# OpenBook_Schematic.net
KiCad netlist of a schematic drawn in EAGLE
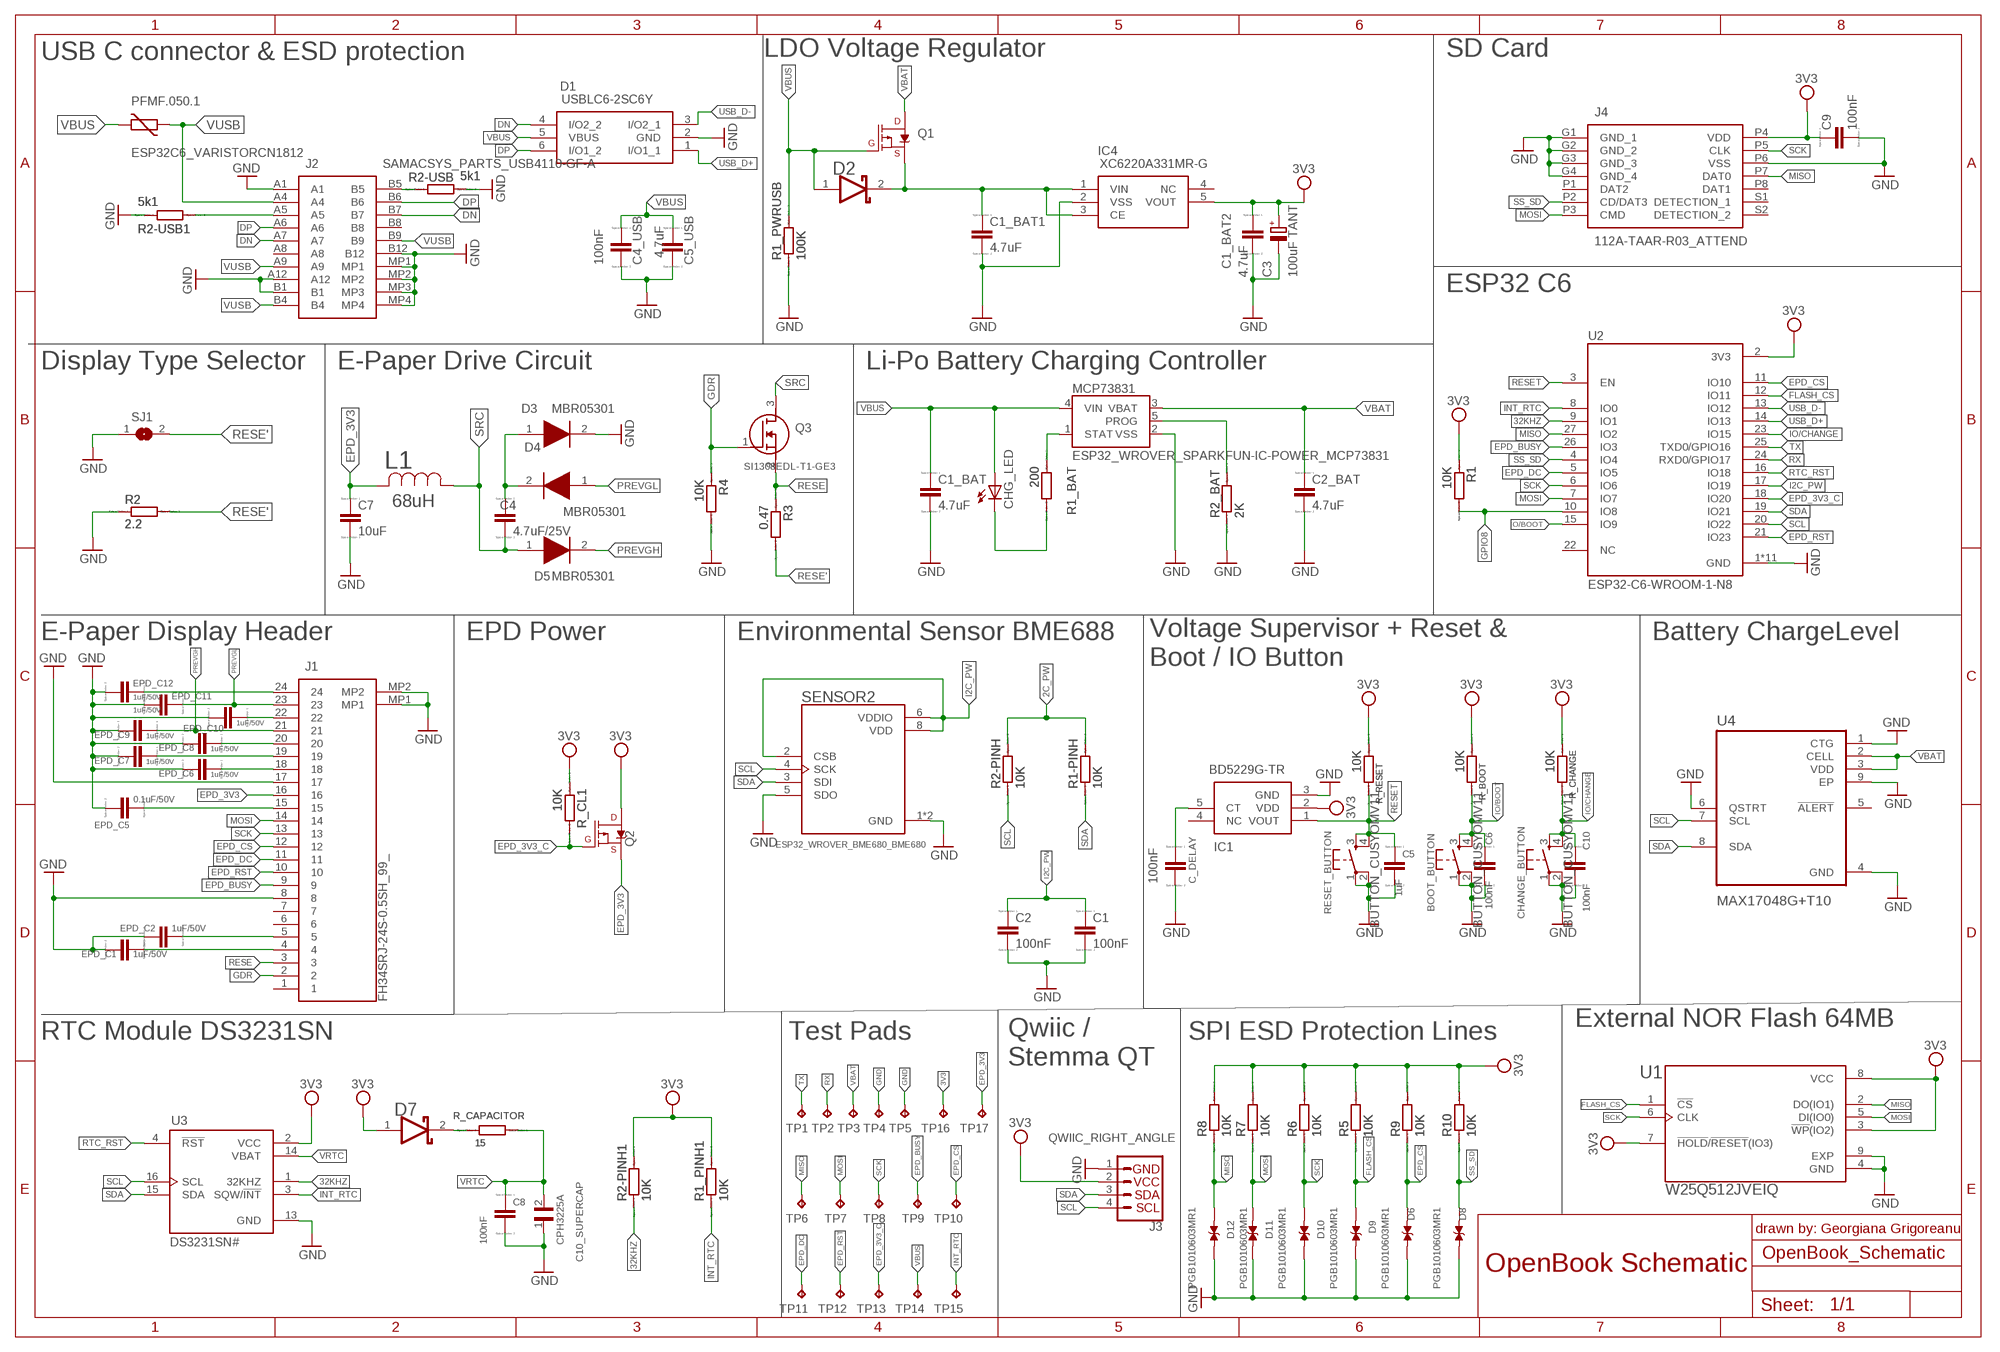
[diagram p0: schematic, sheet 1]

(export (version "E")
  (design (tool "Eeschema 10.0.6"))
  (components
    (comp (ref "BOOT_BUTTON")
      (value "BUTTON_CUSYOMV11")
      (footprint "eagle-import:MYBUTTON")
      (libsource (lib "eagle-import") (part "BUTTON_CUSYOMV11"))
    )
    (comp (ref "C1")
      (value "100nF")
      (footprint "eagle-import:ESP32_WROVER_EAGLE-LTSPICE_C0402")
      (libsource (lib "eagle-import") (part "ESP32_WROVER_EAGLE-LTSPICE_C"))
    )
    (comp (ref "C1_BAT")
      (value "4.7uF")
      (footprint "eagle-import:ESP32_WROVER_EAGLE-LTSPICE_C0402")
      (libsource (lib "eagle-import") (part "ESP32_WROVER_EAGLE-LTSPICE_C"))
    )
    (comp (ref "C1_BAT1")
      (value "4.7uF")
      (footprint "eagle-import:ESP32_WROVER_EAGLE-LTSPICE_C0402")
      (libsource (lib "eagle-import") (part "ESP32_WROVER_EAGLE-LTSPICE_C"))
    )
    (comp (ref "C1_BAT2")
      (value "4.7uF")
      (footprint "eagle-import:ESP32_WROVER_EAGLE-LTSPICE_C0402")
      (libsource (lib "eagle-import") (part "ESP32_WROVER_EAGLE-LTSPICE_C"))
    )
    (comp (ref "C2")
      (value "100nF")
      (footprint "eagle-import:ESP32_WROVER_EAGLE-LTSPICE_C0402")
      (libsource (lib "eagle-import") (part "ESP32_WROVER_EAGLE-LTSPICE_C"))
    )
    (comp (ref "C2_BAT")
      (value "4.7uF")
      (footprint "eagle-import:ESP32_WROVER_EAGLE-LTSPICE_C0402")
      (libsource (lib "eagle-import") (part "ESP32_WROVER_EAGLE-LTSPICE_C"))
    )
    (comp (ref "C3")
      (value "100uF TANT")
      (footprint "eagle-import:RCL_CT3528")
      (libsource (lib "eagle-import") (part "RCL_CPOL-EUCT3528"))
    )
    (comp (ref "C4")
      (value "4.7uF/25V")
      (footprint "eagle-import:ESP32_WROVER_EAGLE-LTSPICE_C0402")
      (libsource (lib "eagle-import") (part "ESP32_WROVER_EAGLE-LTSPICE_C"))
    )
    (comp (ref "C4_USB")
      (value "100nF")
      (footprint "eagle-import:ESP32_WROVER_EAGLE-LTSPICE_C0402")
      (libsource (lib "eagle-import") (part "ESP32_WROVER_EAGLE-LTSPICE_C"))
    )
    (comp (ref "C5")
      (value "1uF")
      (footprint "eagle-import:ESP32_WROVER_EAGLE-LTSPICE_C0402")
      (libsource (lib "eagle-import") (part "ESP32_WROVER_EAGLE-LTSPICE_C"))
    )
    (comp (ref "C5_USB")
      (value "4.7uF")
      (footprint "eagle-import:ESP32_WROVER_EAGLE-LTSPICE_C0402")
      (libsource (lib "eagle-import") (part "ESP32_WROVER_EAGLE-LTSPICE_C"))
    )
    (comp (ref "C6")
      (value "100nF")
      (footprint "eagle-import:ESP32_WROVER_EAGLE-LTSPICE_C0402")
      (libsource (lib "eagle-import") (part "ESP32_WROVER_EAGLE-LTSPICE_C"))
    )
    (comp (ref "C7")
      (value "10uF")
      (footprint "eagle-import:ESP32_WROVER_EAGLE-LTSPICE_C0402")
      (libsource (lib "eagle-import") (part "ESP32_WROVER_EAGLE-LTSPICE_C"))
    )
    (comp (ref "C8")
      (value "100nF")
      (footprint "eagle-import:ESP32_WROVER_EAGLE-LTSPICE_C0402")
      (libsource (lib "eagle-import") (part "ESP32_WROVER_EAGLE-LTSPICE_C"))
    )
    (comp (ref "C9")
      (value "100nF")
      (footprint "eagle-import:ESP32_WROVER_EAGLE-LTSPICE_C0402")
      (libsource (lib "eagle-import") (part "ESP32_WROVER_EAGLE-LTSPICE_C"))
    )
    (comp (ref "C10")
      (value "100nF")
      (footprint "eagle-import:ESP32_WROVER_EAGLE-LTSPICE_C0402")
      (libsource (lib "eagle-import") (part "ESP32_WROVER_EAGLE-LTSPICE_C"))
    )
    (comp (ref "C10_SUPERCAP")
      (value "CPH3225A")
      (footprint "eagle-import:CAPCP3225X100N")
      (fields (field (name "MF") "Seiko Instruments"))
      (libsource (lib "eagle-import") (part "CPH3225A"))
    )
    (comp (ref "CHANGE_BUTTON")
      (value "BUTTON_CUSYOMV11")
      (footprint "eagle-import:MYBUTTON")
      (libsource (lib "eagle-import") (part "BUTTON_CUSYOMV11"))
    )
    (comp (ref "CHG_LED")
      (value "ADAFRUIT_LEDCHIP-LED0603")
      (footprint "eagle-import:ADAFRUIT_CHIP-LED0603")
      (libsource (lib "eagle-import") (part "ADAFRUIT_LEDCHIP-LED0603"))
    )
    (comp (ref "C_DELAY")
      (value "100nF")
      (footprint "eagle-import:ESP32_WROVER_EAGLE-LTSPICE_C0402")
      (libsource (lib "eagle-import") (part "ESP32_WROVER_EAGLE-LTSPICE_C"))
    )
    (comp (ref "D1")
      (value "USBLC6-2SC6Y")
      (footprint "eagle-import:SOT95P280X145-6N")
      (fields (field (name "MF") "STMicroelectronics"))
      (libsource (lib "eagle-import") (part "USBLC6-2SC6Y"))
    )
    (comp (ref "D2")
      (value "ESP32_WROVER_AVX---SD0805S020S1R0_AVX_SD0805S020S1R0_0_0")
      (footprint "eagle-import:ESP32_WROVER_AVX---SD0805S020S1R0_AVX_SD0805S020S1R0_0")
      (libsource (lib "eagle-import") (part "ESP32_WROVER_AVX---SD0805S020S1R0_AVX_SD0805S020S1R0_0_0"))
    )
    (comp (ref "D3")
      (value "MBR05301")
      (footprint "eagle-import:SOD3716X135N")
      (libsource (lib "eagle-import") (part "MBR05301"))
    )
    (comp (ref "D4")
      (value "MBR05301")
      (footprint "eagle-import:SOD3716X135N")
      (libsource (lib "eagle-import") (part "MBR05301"))
    )
    (comp (ref "D5")
      (value "MBR05301")
      (footprint "eagle-import:SOD3716X135N")
      (libsource (lib "eagle-import") (part "MBR05301"))
    )
    (comp (ref "D6")
      (value "PGB1010603MR1")
      (footprint "eagle-import:DIOC1608X36N")
      (libsource (lib "eagle-import") (part "PGB1010603MR1"))
    )
    (comp (ref "D7")
      (value "ESP32_WROVER_AVX---SD0805S020S1R0_AVX_SD0805S020S1R0_0_0")
      (footprint "eagle-import:ESP32_WROVER_AVX---SD0805S020S1R0_AVX_SD0805S020S1R0_0")
      (libsource (lib "eagle-import") (part "ESP32_WROVER_AVX---SD0805S020S1R0_AVX_SD0805S020S1R0_0_0"))
    )
    (comp (ref "D8")
      (value "PGB1010603MR1")
      (footprint "eagle-import:DIOC1608X36N")
      (libsource (lib "eagle-import") (part "PGB1010603MR1"))
    )
    (comp (ref "D9")
      (value "PGB1010603MR1")
      (footprint "eagle-import:DIOC1608X36N")
      (libsource (lib "eagle-import") (part "PGB1010603MR1"))
    )
    (comp (ref "D10")
      (value "PGB1010603MR1")
      (footprint "eagle-import:DIOC1608X36N")
      (libsource (lib "eagle-import") (part "PGB1010603MR1"))
    )
    (comp (ref "D11")
      (value "PGB1010603MR1")
      (footprint "eagle-import:DIOC1608X36N")
      (libsource (lib "eagle-import") (part "PGB1010603MR1"))
    )
    (comp (ref "D12")
      (value "PGB1010603MR1")
      (footprint "eagle-import:DIOC1608X36N")
      (libsource (lib "eagle-import") (part "PGB1010603MR1"))
    )
    (comp (ref "EPD_C1")
      (value "1uF/50V")
      (footprint "eagle-import:ESP32_WROVER_EAGLE-LTSPICE_C0402")
      (libsource (lib "eagle-import") (part "ESP32_WROVER_EAGLE-LTSPICE_C"))
    )
    (comp (ref "EPD_C2")
      (value "1uF/50V")
      (footprint "eagle-import:ESP32_WROVER_EAGLE-LTSPICE_C0402")
      (libsource (lib "eagle-import") (part "ESP32_WROVER_EAGLE-LTSPICE_C"))
    )
    (comp (ref "EPD_C5")
      (value "0.1uF/50V")
      (footprint "eagle-import:ESP32_WROVER_EAGLE-LTSPICE_C0402")
      (libsource (lib "eagle-import") (part "ESP32_WROVER_EAGLE-LTSPICE_C"))
    )
    (comp (ref "EPD_C6")
      (value "1uF/50V")
      (footprint "eagle-import:ESP32_WROVER_EAGLE-LTSPICE_C0402")
      (libsource (lib "eagle-import") (part "ESP32_WROVER_EAGLE-LTSPICE_C"))
    )
    (comp (ref "EPD_C7")
      (value "1uF/50V")
      (footprint "eagle-import:ESP32_WROVER_EAGLE-LTSPICE_C0402")
      (libsource (lib "eagle-import") (part "ESP32_WROVER_EAGLE-LTSPICE_C"))
    )
    (comp (ref "EPD_C8")
      (value "1uF/50V")
      (footprint "eagle-import:ESP32_WROVER_EAGLE-LTSPICE_C0402")
      (libsource (lib "eagle-import") (part "ESP32_WROVER_EAGLE-LTSPICE_C"))
    )
    (comp (ref "EPD_C9")
      (value "1uF/50V")
      (footprint "eagle-import:ESP32_WROVER_EAGLE-LTSPICE_C0402")
      (libsource (lib "eagle-import") (part "ESP32_WROVER_EAGLE-LTSPICE_C"))
    )
    (comp (ref "EPD_C10")
      (value "1uF/50V")
      (footprint "eagle-import:ESP32_WROVER_EAGLE-LTSPICE_C0402")
      (libsource (lib "eagle-import") (part "ESP32_WROVER_EAGLE-LTSPICE_C"))
    )
    (comp (ref "EPD_C11")
      (value "1uF/50V")
      (footprint "eagle-import:ESP32_WROVER_EAGLE-LTSPICE_C0402")
      (libsource (lib "eagle-import") (part "ESP32_WROVER_EAGLE-LTSPICE_C"))
    )
    (comp (ref "EPD_C12")
      (value "1uF/50V")
      (footprint "eagle-import:ESP32_WROVER_EAGLE-LTSPICE_C0402")
      (libsource (lib "eagle-import") (part "ESP32_WROVER_EAGLE-LTSPICE_C"))
    )
    (comp (ref "IC1")
      (value "BD5229G-TR")
      (footprint "eagle-import:SOT95P280X125-5N")
      (fields (field (name "MOUSER_PART_NUMBER") "755-BD5229G-TR"))
      (libsource (lib "eagle-import") (part "BD5229G-TR"))
    )
    (comp (ref "IC4")
      (value "XC6220A331MR-G")
      (footprint "eagle-import:SOT95P280X120-5N")
      (fields (field (name "MOUSER_PART_NUMBER") "865-XC6220A331MR-G"))
      (libsource (lib "eagle-import") (part "XC6220A331MR-G"))
    )
    (comp (ref "J1")
      (value "FH34SRJ-24S-0.5SH_99_")
      (footprint "eagle-import:FH34SRJ24S05SH99")
      (fields
        (field (name "MANUFACTURER_PART_NUMBER") "FH34SRJ-24S-0.5SH(99)")
        (field (name "MOUSER_PART_NUMBER") "798-FH34SRJ24S05SH99")
      )
      (libsource (lib "eagle-import") (part "FH34SRJ-24S-0.5SH_99_"))
    )
    (comp (ref "J2")
      (value "SAMACSYS_PARTS_USB4110-GF-A")
      (footprint "eagle-import:SAMACSYS_PARTS_USB4110GFA")
      (fields
        (field (name "MANUFACTURER_PART_NUMBER") "USB4110-GF-A")
        (field (name "MOUSER_PART_NUMBER") "640-USB4110-GF-A")
      )
      (libsource (lib "eagle-import") (part "SAMACSYS_PARTS_USB4110-GF-A"))
    )
    (comp (ref "J3")
      (value "QWIIC_RIGHT_ANGLE")
      (footprint "eagle-import:JST04_1MM_RA")
      (libsource (lib "eagle-import") (part "QWIIC_CONNECTORJS-1MM"))
    )
    (comp (ref "J4")
      (value "112A-TAAR-R03_ATTEND")
      (footprint "eagle-import:112ATAARR03ATTEND")
      (fields (field (name "MANUFACTURER_PART_NUMBER") "112A-TAAR-R03 ATTEND"))
      (libsource (lib "eagle-import") (part "112A-TAAR-R03_ATTEND"))
    )
    (comp (ref "L1")
      (value "68uH")
      (footprint "eagle-import:IND_4828-WE-TPC_WRE")
      (fields
        (field (name "MANUFACTURER_PART_NUMBER") "744043680")
        (field (name "COPYRIGHT") "Copyright (C) 2024 Ultra Librarian. All rights reserved.")
      )
      (libsource (lib "eagle-import") (part "744043680IND_4828-WE-TPC_WRE"))
    )
    (comp (ref "MCP73831")
      (value "ESP32_WROVER_SPARKFUN-IC-POWER_MCP73831")
      (footprint "eagle-import:ESP32_WROVER_SPARKFUN-IC-POWER_SOT23-5")
      (libsource (lib "eagle-import") (part "ESP32_WROVER_SPARKFUN-IC-POWER_MCP73831"))
    )
    (comp (ref "PFMF.050.1")
      (value "ESP32C6_VARISTORCN1812")
      (footprint "eagle-import:ESP32C6_VARISTOR_CT_CN1812")
      (libsource (lib "eagle-import") (part "ESP32C6_VARISTORCN1812"))
    )
    (comp (ref "Q1")
      (value "20V/4.2A/52mΩ/1.4W")
      (footprint "eagle-import:ESP32_WROVER_SPARKFUN-DISCRETESEMI_SOT23-3")
      (libsource (lib "eagle-import") (part "ESP32_WROVER_SPARKFUN-DISCRETESEMI_MOSFET_PCH"))
    )
    (comp (ref "Q2")
      (value "20V/4.2A/52mΩ/1.4W")
      (footprint "eagle-import:ESP32_WROVER_SPARKFUN-DISCRETESEMI_SOT23-3")
      (libsource (lib "eagle-import") (part "ESP32_WROVER_SPARKFUN-DISCRETESEMI_MOSFET_PCH"))
    )
    (comp (ref "Q3")
      (value "SI1308EDL-T1-GE3")
      (footprint "eagle-import:SOT65P210X110-3N")
      (fields (field (name "MF") "Vishay Siliconix"))
      (libsource (lib "eagle-import") (part "SI1308EDL-T1-GE3"))
    )
    (comp (ref "R1")
      (value "10K")
      (footprint "eagle-import:ESP32_WROVER_EAGLE-LTSPICE_C0402")
      (libsource (lib "eagle-import") (part "ESP32_WROVER_EAGLE-LTSPICE_R1"))
    )
    (comp (ref "R1-PINH")
      (value "10K")
      (footprint "eagle-import:ESP32_WROVER_EAGLE-LTSPICE_C0402")
      (libsource (lib "eagle-import") (part "ESP32_WROVER_EAGLE-LTSPICE_R1"))
    )
    (comp (ref "R1_BAT")
      (value "200")
      (footprint "eagle-import:ESP32_WROVER_EAGLE-LTSPICE_C0402")
      (libsource (lib "eagle-import") (part "ESP32_WROVER_EAGLE-LTSPICE_R1"))
    )
    (comp (ref "R1_PINH1")
      (value "10K")
      (footprint "eagle-import:ESP32_WROVER_EAGLE-LTSPICE_C0402")
      (libsource (lib "eagle-import") (part "ESP32_WROVER_EAGLE-LTSPICE_R1"))
    )
    (comp (ref "R1_PWRUSB")
      (value "100K")
      (footprint "eagle-import:ESP32_WROVER_EAGLE-LTSPICE_C0402")
      (libsource (lib "eagle-import") (part "ESP32_WROVER_EAGLE-LTSPICE_R1"))
    )
    (comp (ref "R2")
      (value "2.2")
      (footprint "eagle-import:ESP32_WROVER_EAGLE-LTSPICE_C0402")
      (libsource (lib "eagle-import") (part "ESP32_WROVER_EAGLE-LTSPICE_R1"))
    )
    (comp (ref "R2-PINH")
      (value "10K")
      (footprint "eagle-import:ESP32_WROVER_EAGLE-LTSPICE_C0402")
      (libsource (lib "eagle-import") (part "ESP32_WROVER_EAGLE-LTSPICE_R1"))
    )
    (comp (ref "R2-PINH1")
      (value "10K")
      (footprint "eagle-import:ESP32_WROVER_EAGLE-LTSPICE_C0402")
      (libsource (lib "eagle-import") (part "ESP32_WROVER_EAGLE-LTSPICE_R1"))
    )
    (comp (ref "R2-USB")
      (value "5k1")
      (footprint "eagle-import:ESP32_WROVER_EAGLE-LTSPICE_C0402")
      (libsource (lib "eagle-import") (part "ESP32_WROVER_EAGLE-LTSPICE_R1"))
    )
    (comp (ref "R2-USB1")
      (value "5k1")
      (footprint "eagle-import:ESP32_WROVER_EAGLE-LTSPICE_C0402")
      (libsource (lib "eagle-import") (part "ESP32_WROVER_EAGLE-LTSPICE_R1"))
    )
    (comp (ref "R2_BAT")
      (value "2K")
      (footprint "eagle-import:ESP32_WROVER_EAGLE-LTSPICE_C0402")
      (libsource (lib "eagle-import") (part "ESP32_WROVER_EAGLE-LTSPICE_R1"))
    )
    (comp (ref "R3")
      (value "0.47")
      (footprint "eagle-import:ESP32_WROVER_EAGLE-LTSPICE_C0402")
      (libsource (lib "eagle-import") (part "ESP32_WROVER_EAGLE-LTSPICE_R1"))
    )
    (comp (ref "R4")
      (value "10K")
      (footprint "eagle-import:ESP32_WROVER_EAGLE-LTSPICE_C0402")
      (libsource (lib "eagle-import") (part "ESP32_WROVER_EAGLE-LTSPICE_R1"))
    )
    (comp (ref "R5")
      (value "10K")
      (footprint "eagle-import:ESP32_WROVER_EAGLE-LTSPICE_C0402")
      (libsource (lib "eagle-import") (part "ESP32_WROVER_EAGLE-LTSPICE_R1"))
    )
    (comp (ref "R6")
      (value "10K")
      (footprint "eagle-import:ESP32_WROVER_EAGLE-LTSPICE_C0402")
      (libsource (lib "eagle-import") (part "ESP32_WROVER_EAGLE-LTSPICE_R1"))
    )
    (comp (ref "R7")
      (value "10K")
      (footprint "eagle-import:ESP32_WROVER_EAGLE-LTSPICE_C0402")
      (libsource (lib "eagle-import") (part "ESP32_WROVER_EAGLE-LTSPICE_R1"))
    )
    (comp (ref "R8")
      (value "10K")
      (footprint "eagle-import:ESP32_WROVER_EAGLE-LTSPICE_C0402")
      (libsource (lib "eagle-import") (part "ESP32_WROVER_EAGLE-LTSPICE_R1"))
    )
    (comp (ref "R9")
      (value "10K")
      (footprint "eagle-import:ESP32_WROVER_EAGLE-LTSPICE_C0402")
      (libsource (lib "eagle-import") (part "ESP32_WROVER_EAGLE-LTSPICE_R1"))
    )
    (comp (ref "R10")
      (value "10K")
      (footprint "eagle-import:ESP32_WROVER_EAGLE-LTSPICE_C0402")
      (libsource (lib "eagle-import") (part "ESP32_WROVER_EAGLE-LTSPICE_R1"))
    )
    (comp (ref "RESET_BUTTON")
      (value "BUTTON_CUSYOMV11")
      (footprint "eagle-import:MYBUTTON")
      (libsource (lib "eagle-import") (part "BUTTON_CUSYOMV11"))
    )
    (comp (ref "R_BOOT")
      (value "10K")
      (footprint "eagle-import:ESP32_WROVER_EAGLE-LTSPICE_C0402")
      (libsource (lib "eagle-import") (part "ESP32_WROVER_EAGLE-LTSPICE_R1"))
    )
    (comp (ref "R_CAPACITOR")
      (value "15")
      (footprint "eagle-import:ESP32_WROVER_EAGLE-LTSPICE_C0402")
      (libsource (lib "eagle-import") (part "ESP32_WROVER_EAGLE-LTSPICE_R1"))
    )
    (comp (ref "R_CHANGE")
      (value "10K")
      (footprint "eagle-import:ESP32_WROVER_EAGLE-LTSPICE_C0402")
      (libsource (lib "eagle-import") (part "ESP32_WROVER_EAGLE-LTSPICE_R1"))
    )
    (comp (ref "R_CL1")
      (value "10K")
      (footprint "eagle-import:ESP32_WROVER_EAGLE-LTSPICE_C0402")
      (libsource (lib "eagle-import") (part "ESP32_WROVER_EAGLE-LTSPICE_R1"))
    )
    (comp (ref "R_RESET")
      (value "10K")
      (footprint "eagle-import:ESP32_WROVER_EAGLE-LTSPICE_C0402")
      (libsource (lib "eagle-import") (part "ESP32_WROVER_EAGLE-LTSPICE_R1"))
    )
    (comp (ref "SENSOR2")
      (value "ESP32_WROVER_BME680_BME680")
      (footprint "eagle-import:ESP32_WROVER_BME680_PSON80P300X300X100-8N")
      (fields (field (name "MF") "Bosch Sensortec") (field (name "MP") "BME680"))
      (libsource (lib "eagle-import") (part "ESP32_WROVER_BME680_BME680"))
    )
    (comp (ref "SJ1") (value "SJ") (footprint "eagle-import:SJ") (libsource (lib "eagle-import") (part "SJ")))
    (comp (ref "TP1")
      (value "TP")
      (footprint "eagle-import:TP20R")
      (libsource (lib "eagle-import") (part "TP"))
    )
    (comp (ref "TP2")
      (value "TP")
      (footprint "eagle-import:TP20R")
      (libsource (lib "eagle-import") (part "TP"))
    )
    (comp (ref "TP3")
      (value "TP")
      (footprint "eagle-import:TP20R")
      (libsource (lib "eagle-import") (part "TP"))
    )
    (comp (ref "TP4")
      (value "TP")
      (footprint "eagle-import:TP20R")
      (libsource (lib "eagle-import") (part "TP"))
    )
    (comp (ref "TP5")
      (value "TP")
      (footprint "eagle-import:TP20R")
      (libsource (lib "eagle-import") (part "TP"))
    )
    (comp (ref "TP6")
      (value "TP")
      (footprint "eagle-import:TP20R")
      (libsource (lib "eagle-import") (part "TP"))
    )
    (comp (ref "TP7")
      (value "TP")
      (footprint "eagle-import:TP20R")
      (libsource (lib "eagle-import") (part "TP"))
    )
    (comp (ref "TP8")
      (value "TP")
      (footprint "eagle-import:TP20R")
      (libsource (lib "eagle-import") (part "TP"))
    )
    (comp (ref "TP9")
      (value "TP")
      (footprint "eagle-import:TP20R")
      (libsource (lib "eagle-import") (part "TP"))
    )
    (comp (ref "TP10")
      (value "TP")
      (footprint "eagle-import:TP20R")
      (libsource (lib "eagle-import") (part "TP"))
    )
    (comp (ref "TP11")
      (value "TP")
      (footprint "eagle-import:TP20R")
      (libsource (lib "eagle-import") (part "TP"))
    )
    (comp (ref "TP12")
      (value "TP")
      (footprint "eagle-import:TP20R")
      (libsource (lib "eagle-import") (part "TP"))
    )
    (comp (ref "TP13")
      (value "TP")
      (footprint "eagle-import:TP20R")
      (libsource (lib "eagle-import") (part "TP"))
    )
    (comp (ref "TP14")
      (value "TP")
      (footprint "eagle-import:TP20R")
      (libsource (lib "eagle-import") (part "TP"))
    )
    (comp (ref "TP15")
      (value "TP")
      (footprint "eagle-import:TP20R")
      (libsource (lib "eagle-import") (part "TP"))
    )
    (comp (ref "TP16")
      (value "TP")
      (footprint "eagle-import:TP20R")
      (libsource (lib "eagle-import") (part "TP"))
    )
    (comp (ref "TP17")
      (value "TP")
      (footprint "eagle-import:TP20R")
      (libsource (lib "eagle-import") (part "TP"))
    )
    (comp (ref "U1")
      (value "W25Q512JVEIQ")
      (footprint "eagle-import:SON127P600X800X80-9N")
      (fields (field (name "MF") "Winbond Electronics"))
      (libsource (lib "eagle-import") (part "W25Q512JVEIQ"))
    )
    (comp (ref "U2")
      (value "ESP32-C6-WROOM-1-N8")
      (footprint "eagle-import:XCVR_ESP32-C6-WROOM-1-N8")
      (fields (field (name "MF") "Espressif Systems"))
      (libsource (lib "eagle-import") (part "ESP32-C6-WROOM-1-N8"))
    )
    (comp (ref "U3")
      (value "DS3231SN#")
      (footprint "eagle-import:SOIC127P1032X265-16N")
      (fields (field (name "MF") "Analog Devices"))
      (libsource (lib "eagle-import") (part "DS3231SN#"))
    )
    (comp (ref "U4")
      (value "MAX17048G+T10")
      (footprint "eagle-import:SON50P200X200X80-9N")
      (fields (field (name "MF") "Analog Devices"))
      (libsource (lib "eagle-import") (part "MAX17048G+T10"))
    )
  )
  (nets
    (net (code "1") (name "2C_PW") (class "Default")
      (node (ref "R1-PINH") (pin "2") (pinfunction "2_2") (pintype "passive"))
      (node (ref "R2-PINH") (pin "2") (pinfunction "2_2") (pintype "passive"))
    )
    (net (code "2") (name "3V3") (class "Default")
      (node (ref "C1_BAT2") (pin "1") (pinfunction "1_1") (pintype "passive"))
      (node (ref "C3") (pin "+") (pinfunction "+_+") (pintype "passive"))
      (node (ref "C9") (pin "1") (pinfunction "1_1") (pintype "passive"))
      (node (ref "D7") (pin "1") (pinfunction "ANODE_1") (pintype "bidirectional"))
      (node (ref "IC1") (pin "2") (pinfunction "VDD_2") (pintype "bidirectional"))
      (node (ref "IC4") (pin "5") (pinfunction "VOUT_5") (pintype "bidirectional"))
      (node (ref "J3") (pin "2") (pinfunction "2_2") (pintype "power_in"))
      (node (ref "J4") (pin "P4") (pinfunction "VDD_P4") (pintype "bidirectional"))
      (node (ref "Q2") (pin "1") (pinfunction "D_1") (pintype "bidirectional"))
      (node (ref "R1") (pin "1") (pinfunction "1_1") (pintype "passive"))
      (node (ref "R10") (pin "2") (pinfunction "2_2") (pintype "passive"))
      (node (ref "R1_PINH1") (pin "2") (pinfunction "2_2") (pintype "passive"))
      (node (ref "R2-PINH1") (pin "2") (pinfunction "2_2") (pintype "passive"))
      (node (ref "R5") (pin "2") (pinfunction "2_2") (pintype "passive"))
      (node (ref "R6") (pin "2") (pinfunction "2_2") (pintype "passive"))
      (node (ref "R7") (pin "2") (pinfunction "2_2") (pintype "passive"))
      (node (ref "R8") (pin "2") (pinfunction "2_2") (pintype "passive"))
      (node (ref "R9") (pin "2") (pinfunction "2_2") (pintype "passive"))
      (node (ref "R_BOOT") (pin "1") (pinfunction "1_1") (pintype "passive"))
      (node (ref "R_CHANGE") (pin "1") (pinfunction "1_1") (pintype "passive"))
      (node (ref "R_CL1") (pin "1") (pinfunction "1_1") (pintype "passive"))
      (node (ref "R_RESET") (pin "1") (pinfunction "1_1") (pintype "passive"))
      (node (ref "TP16") (pin "TP") (pinfunction "TP_TP") (pintype "input"))
      (node (ref "U1") (pin "3") (pinfunction "~{WP}(IO2)_3") (pintype "bidirectional"))
      (node (ref "U1") (pin "7") (pinfunction "~{HOLD}/~{RESET}(IO3)_7") (pintype "bidirectional"))
      (node (ref "U1") (pin "8") (pinfunction "VCC_8") (pintype "power_in"))
      (node (ref "U2") (pin "2") (pinfunction "3V3_2") (pintype "power_in"))
      (node (ref "U3") (pin "2") (pinfunction "VCC_2") (pintype "power_in"))
    )
    (net (code "3") (name "32KHZ") (class "Default")
      (node (ref "R2-PINH1") (pin "1") (pinfunction "1_1") (pintype "passive"))
      (node (ref "U2") (pin "9") (pinfunction "IO1_9") (pintype "bidirectional"))
      (node (ref "U3") (pin "1") (pinfunction "32KHZ_1") (pintype "output"))
    )
    (net (code "4") (name "DN") (class "Default")
      (node (ref "D1") (pin "4") (pinfunction "I/O2_2_4") (pintype "bidirectional"))
      (node (ref "J2") (pin "A7") (pinfunction "A7_A7") (pintype "bidirectional"))
      (node (ref "J2") (pin "B7") (pinfunction "B7_B7") (pintype "bidirectional"))
    )
    (net (code "5") (name "DP") (class "Default")
      (node (ref "D1") (pin "6") (pinfunction "I/O1_2_6") (pintype "bidirectional"))
      (node (ref "J2") (pin "A6") (pinfunction "A6_A6") (pintype "bidirectional"))
      (node (ref "J2") (pin "B6") (pinfunction "B6_B6") (pintype "bidirectional"))
    )
    (net (code "6") (name "EPD_3V3") (class "Default")
      (node (ref "C7") (pin "1") (pinfunction "1_1") (pintype "passive"))
      (node (ref "J1") (pin "16") (pinfunction "16_16") (pintype "bidirectional"))
      (node (ref "L1") (pin "2") (pinfunction "2_2") (pintype "passive"))
      (node (ref "Q2") (pin "3") (pinfunction "S_3") (pintype "bidirectional"))
      (node (ref "TP17") (pin "TP") (pinfunction "TP_TP") (pintype "input"))
    )
    (net (code "7") (name "EPD_3V3_C") (class "Default")
      (node (ref "Q2") (pin "2") (pinfunction "G_2") (pintype "bidirectional"))
      (node (ref "R_CL1") (pin "2") (pinfunction "2_2") (pintype "passive"))
      (node (ref "TP13") (pin "TP") (pinfunction "TP_TP") (pintype "input"))
      (node (ref "U2") (pin "18") (pinfunction "IO20_18") (pintype "bidirectional"))
    )
    (net (code "8") (name "EPD_BUSY") (class "Default")
      (node (ref "J1") (pin "9") (pinfunction "9_9") (pintype "bidirectional"))
      (node (ref "TP9") (pin "TP") (pinfunction "TP_TP") (pintype "input"))
      (node (ref "U2") (pin "26") (pinfunction "IO3_26") (pintype "bidirectional"))
    )
    (net (code "9") (name "EPD_CS") (class "Default")
      (node (ref "D6") (pin "1") (pinfunction "1_1") (pintype "passive"))
      (node (ref "J1") (pin "12") (pinfunction "12_12") (pintype "bidirectional"))
      (node (ref "R9") (pin "1") (pinfunction "1_1") (pintype "passive"))
      (node (ref "TP10") (pin "TP") (pinfunction "TP_TP") (pintype "input"))
      (node (ref "U2") (pin "11") (pinfunction "IO10_11") (pintype "bidirectional"))
    )
    (net (code "10") (name "EPD_DC") (class "Default")
      (node (ref "J1") (pin "11") (pinfunction "11_11") (pintype "bidirectional"))
      (node (ref "TP11") (pin "TP") (pinfunction "TP_TP") (pintype "input"))
      (node (ref "U2") (pin "5") (pinfunction "IO5_5") (pintype "bidirectional"))
    )
    (net (code "11") (name "EPD_RST") (class "Default")
      (node (ref "J1") (pin "10") (pinfunction "10_10") (pintype "bidirectional"))
      (node (ref "TP12") (pin "TP") (pinfunction "TP_TP") (pintype "input"))
      (node (ref "U2") (pin "21") (pinfunction "IO23_21") (pintype "bidirectional"))
    )
    (net (code "12") (name "FLASH_CS") (class "Default")
      (node (ref "D9") (pin "1") (pinfunction "1_1") (pintype "passive"))
      (node (ref "R5") (pin "1") (pinfunction "1_1") (pintype "passive"))
      (node (ref "U1") (pin "1") (pinfunction "~{CS}_1") (pintype "input"))
      (node (ref "U2") (pin "12") (pinfunction "IO11_12") (pintype "bidirectional"))
    )
    (net (code "13") (name "GDR") (class "Default")
      (node (ref "J1") (pin "2") (pinfunction "2_2") (pintype "bidirectional"))
      (node (ref "Q3") (pin "1") (pinfunction "G_1") (pintype "bidirectional"))
      (node (ref "R4") (pin "1") (pinfunction "1_1") (pintype "passive"))
    )
    (net (code "14") (name "GND") (class "Default")
      (node (ref "BOOT_BUTTON") (pin "1") (pinfunction "1_1") (pintype "passive"))
      (node (ref "BOOT_BUTTON") (pin "2") (pinfunction "2_2") (pintype "passive"))
      (node (ref "C1") (pin "2") (pinfunction "2_2") (pintype "passive"))
      (node (ref "C10") (pin "2") (pinfunction "2_2") (pintype "passive"))
      (node (ref "C10_SUPERCAP") (pin "1") (pinfunction "1_1") (pintype "passive"))
      (node (ref "C1_BAT") (pin "2") (pinfunction "2_2") (pintype "passive"))
      (node (ref "C1_BAT1") (pin "2") (pinfunction "2_2") (pintype "passive"))
      (node (ref "C1_BAT2") (pin "2") (pinfunction "2_2") (pintype "passive"))
      (node (ref "C2") (pin "2") (pinfunction "2_2") (pintype "passive"))
      (node (ref "C2_BAT") (pin "2") (pinfunction "2_2") (pintype "passive"))
      (node (ref "C3") (pin "-") (pinfunction "-_-") (pintype "passive"))
      (node (ref "C4_USB") (pin "2") (pinfunction "2_2") (pintype "passive"))
      (node (ref "C5") (pin "2") (pinfunction "2_2") (pintype "passive"))
      (node (ref "C5_USB") (pin "2") (pinfunction "2_2") (pintype "passive"))
      (node (ref "C6") (pin "2") (pinfunction "2_2") (pintype "passive"))
      (node (ref "C7") (pin "2") (pinfunction "2_2") (pintype "passive"))
      (node (ref "C8") (pin "2") (pinfunction "2_2") (pintype "passive"))
      (node (ref "C9") (pin "2") (pinfunction "2_2") (pintype "passive"))
      (node (ref "CHANGE_BUTTON") (pin "1") (pinfunction "1_1") (pintype "passive"))
      (node (ref "CHANGE_BUTTON") (pin "2") (pinfunction "2_2") (pintype "passive"))
      (node (ref "C_DELAY") (pin "2") (pinfunction "2_2") (pintype "passive"))
      (node (ref "D1") (pin "2") (pinfunction "GND_2") (pintype "bidirectional"))
      (node (ref "D10") (pin "2") (pinfunction "2_2") (pintype "passive"))
      (node (ref "D11") (pin "2") (pinfunction "2_2") (pintype "passive"))
      (node (ref "D12") (pin "2") (pinfunction "2_2") (pintype "passive"))
      (node (ref "D3") (pin "2") (pinfunction "K_2") (pintype "bidirectional"))
      (node (ref "D6") (pin "2") (pinfunction "2_2") (pintype "passive"))
      (node (ref "D8") (pin "2") (pinfunction "2_2") (pintype "passive"))
      (node (ref "D9") (pin "2") (pinfunction "2_2") (pintype "passive"))
      (node (ref "EPD_C1") (pin "2") (pinfunction "2_2") (pintype "passive"))
      (node (ref "EPD_C10") (pin "2") (pinfunction "2_2") (pintype "passive"))
      (node (ref "EPD_C11") (pin "2") (pinfunction "2_2") (pintype "passive"))
      (node (ref "EPD_C12") (pin "2") (pinfunction "2_2") (pintype "passive"))
      (node (ref "EPD_C2") (pin "2") (pinfunction "2_2") (pintype "passive"))
      (node (ref "EPD_C5") (pin "2") (pinfunction "2_2") (pintype "passive"))
      (node (ref "EPD_C6") (pin "2") (pinfunction "2_2") (pintype "passive"))
      (node (ref "EPD_C7") (pin "2") (pinfunction "2_2") (pintype "passive"))
      (node (ref "EPD_C8") (pin "2") (pinfunction "2_2") (pintype "passive"))
      (node (ref "EPD_C9") (pin "2") (pinfunction "2_2") (pintype "passive"))
      (node (ref "IC1") (pin "3") (pinfunction "GND_3") (pintype "bidirectional"))
      (node (ref "IC4") (pin "2") (pinfunction "VSS_2") (pintype "bidirectional"))
      (node (ref "J1") (pin "17") (pinfunction "17_17") (pintype "bidirectional"))
      (node (ref "J1") (pin "8") (pinfunction "8_8") (pintype "bidirectional"))
      (node (ref "J1") (pin "MP1") (pinfunction "MP1_MP1") (pintype "bidirectional"))
      (node (ref "J1") (pin "MP2") (pinfunction "MP2_MP2") (pintype "bidirectional"))
      (node (ref "J2") (pin "A1") (pinfunction "A1_A1") (pintype "bidirectional"))
      (node (ref "J2") (pin "A12") (pinfunction "A12_A12") (pintype "bidirectional"))
      (node (ref "J2") (pin "B1") (pinfunction "B1_B1") (pintype "bidirectional"))
      (node (ref "J2") (pin "B12") (pinfunction "B12_B12") (pintype "bidirectional"))
      (node (ref "J2") (pin "MP1") (pinfunction "MP1_MP1") (pintype "bidirectional"))
      (node (ref "J2") (pin "MP2") (pinfunction "MP2_MP2") (pintype "bidirectional"))
      (node (ref "J2") (pin "MP3") (pinfunction "MP3_MP3") (pintype "bidirectional"))
      (node (ref "J2") (pin "MP4") (pinfunction "MP4_MP4") (pintype "bidirectional"))
      (node (ref "J3") (pin "1") (pinfunction "1_1") (pintype "power_in"))
      (node (ref "J4") (pin "G1") (pinfunction "GND_1_G1") (pintype "bidirectional"))
      (node (ref "J4") (pin "G2") (pinfunction "GND_2_G2") (pintype "bidirectional"))
      (node (ref "J4") (pin "G3") (pinfunction "GND_3_G3") (pintype "bidirectional"))
      (node (ref "J4") (pin "G4") (pinfunction "GND_4_G4") (pintype "bidirectional"))
      (node (ref "J4") (pin "P6") (pinfunction "VSS_P6") (pintype "bidirectional"))
      (node (ref "MCP73831") (pin "2") (pinfunction "VSS_2") (pintype "power_in"))
      (node (ref "R1_PWRUSB") (pin "1") (pinfunction "1_1") (pintype "passive"))
      (node (ref "R2") (pin "1") (pinfunction "1_1") (pintype "passive"))
      (node (ref "R2-USB") (pin "2") (pinfunction "2_2") (pintype "passive"))
      (node (ref "R2-USB1") (pin "1") (pinfunction "1_1") (pintype "passive"))
      (node (ref "R2_BAT") (pin "1") (pinfunction "1_1") (pintype "passive"))
      (node (ref "R4") (pin "2") (pinfunction "2_2") (pintype "passive"))
      (node (ref "RESET_BUTTON") (pin "1") (pinfunction "1_1") (pintype "passive"))
      (node (ref "RESET_BUTTON") (pin "2") (pinfunction "2_2") (pintype "passive"))
      (node (ref "SENSOR2") (pin "1") (pinfunction "GND_1") (pintype "power_in"))
      (node (ref "SENSOR2") (pin "5") (pinfunction "SDO_5") (pintype "bidirectional"))
      (node (ref "SENSOR2") (pin "7") (pinfunction "GND_7") (pintype "power_in"))
      (node (ref "SJ1") (pin "1") (pinfunction "1_1") (pintype "passive"))
      (node (ref "TP4") (pin "TP") (pinfunction "TP_TP") (pintype "input"))
      (node (ref "TP5") (pin "TP") (pinfunction "TP_TP") (pintype "input"))
      (node (ref "U1") (pin "4") (pinfunction "GND_4") (pintype "power_in"))
      (node (ref "U1") (pin "9") (pinfunction "EXP_9") (pintype "passive"))
      (node (ref "U2") (pin "1") (pinfunction "GND_1") (pintype "power_in"))
      (node (ref "U2") (pin "28") (pinfunction "GND_28") (pintype "power_in"))
      (node (ref "U2") (pin "29_1") (pinfunction "GND_29_1") (pintype "power_in"))
      (node (ref "U2") (pin "29_2") (pinfunction "GND_29_2") (pintype "power_in"))
      (node (ref "U2") (pin "29_3") (pinfunction "GND_29_3") (pintype "power_in"))
      (node (ref "U2") (pin "29_4") (pinfunction "GND_29_4") (pintype "power_in"))
      (node (ref "U2") (pin "29_5") (pinfunction "GND_29_5") (pintype "power_in"))
      (node (ref "U2") (pin "29_6") (pinfunction "GND_29_6") (pintype "power_in"))
      (node (ref "U2") (pin "29_7") (pinfunction "GND_29_7") (pintype "power_in"))
      (node (ref "U2") (pin "29_8") (pinfunction "GND_29_8") (pintype "power_in"))
      (node (ref "U2") (pin "29_9") (pinfunction "GND_29_9") (pintype "power_in"))
      (node (ref "U3") (pin "13") (pinfunction "GND_13") (pintype "power_in"))
      (node (ref "U4") (pin "1") (pinfunction "CTG_1") (pintype "power_in"))
      (node (ref "U4") (pin "4") (pinfunction "GND_4") (pintype "power_in"))
      (node (ref "U4") (pin "6") (pinfunction "QSTRT_6") (pintype "input"))
      (node (ref "U4") (pin "9") (pinfunction "EP_9") (pintype "power_in"))
    )
    (net (code "15") (name "GPIO8") (class "Default")
      (node (ref "R1") (pin "2") (pinfunction "2_2") (pintype "passive"))
      (node (ref "U2") (pin "10") (pinfunction "IO8_10") (pintype "bidirectional"))
    )
    (net (code "16") (name "I2C_PW") (class "Default")
      (node (ref "C1") (pin "1") (pinfunction "1_1") (pintype "passive"))
      (node (ref "C2") (pin "1") (pinfunction "1_1") (pintype "passive"))
      (node (ref "SENSOR2") (pin "2") (pinfunction "CSB_2") (pintype "input"))
      (node (ref "SENSOR2") (pin "6") (pinfunction "VDDIO_6") (pintype "power_in"))
      (node (ref "SENSOR2") (pin "8") (pinfunction "VDD_8") (pintype "power_in"))
      (node (ref "U2") (pin "17") (pinfunction "IO19_17") (pintype "bidirectional"))
    )
    (net (code "17") (name "INT_RTC") (class "Default")
      (node (ref "R1_PINH1") (pin "1") (pinfunction "1_1") (pintype "passive"))
      (node (ref "TP15") (pin "TP") (pinfunction "TP_TP") (pintype "input"))
      (node (ref "U2") (pin "8") (pinfunction "IO0_8") (pintype "bidirectional"))
      (node (ref "U3") (pin "3") (pinfunction "SQW/~{INT}_3") (pintype "output"))
    )
    (net (code "18") (name "IO{slash}BOOT") (class "Default")
      (node (ref "BOOT_BUTTON") (pin "3") (pinfunction "3_3") (pintype "passive"))
      (node (ref "BOOT_BUTTON") (pin "4") (pinfunction "4_4") (pintype "passive"))
      (node (ref "C6") (pin "1") (pinfunction "1_1") (pintype "passive"))
      (node (ref "R_BOOT") (pin "2") (pinfunction "2_2") (pintype "passive"))
      (node (ref "U2") (pin "15") (pinfunction "IO9_15") (pintype "bidirectional"))
    )
    (net (code "19") (name "IO{slash}CHANGE") (class "Default")
      (node (ref "C10") (pin "1") (pinfunction "1_1") (pintype "passive"))
      (node (ref "CHANGE_BUTTON") (pin "3") (pinfunction "3_3") (pintype "passive"))
      (node (ref "CHANGE_BUTTON") (pin "4") (pinfunction "4_4") (pintype "passive"))
      (node (ref "R_CHANGE") (pin "2") (pinfunction "2_2") (pintype "passive"))
      (node (ref "U2") (pin "23") (pinfunction "IO15_23") (pintype "bidirectional"))
    )
    (net (code "20") (name "MISO") (class "Default")
      (node (ref "D12") (pin "1") (pinfunction "1_1") (pintype "passive"))
      (node (ref "J4") (pin "P7") (pinfunction "DAT0_P7") (pintype "bidirectional"))
      (node (ref "R8") (pin "1") (pinfunction "1_1") (pintype "passive"))
      (node (ref "TP6") (pin "TP") (pinfunction "TP_TP") (pintype "input"))
      (node (ref "U1") (pin "2") (pinfunction "DO(IO1)_2") (pintype "bidirectional"))
      (node (ref "U2") (pin "27") (pinfunction "IO2_27") (pintype "bidirectional"))
    )
    (net (code "21") (name "MOSI") (class "Default")
      (node (ref "D11") (pin "1") (pinfunction "1_1") (pintype "passive"))
      (node (ref "J1") (pin "14") (pinfunction "14_14") (pintype "bidirectional"))
      (node (ref "J4") (pin "P3") (pinfunction "CMD_P3") (pintype "bidirectional"))
      (node (ref "R7") (pin "1") (pinfunction "1_1") (pintype "passive"))
      (node (ref "TP7") (pin "TP") (pinfunction "TP_TP") (pintype "input"))
      (node (ref "U1") (pin "5") (pinfunction "DI(IO0)_5") (pintype "bidirectional"))
      (node (ref "U2") (pin "7") (pinfunction "IO7_7") (pintype "bidirectional"))
    )
    (net (code "22") (name "Net-(CHG_LED-PadC)") (class "Default")
      (node (ref "CHG_LED") (pin "C") (pinfunction "C_C") (pintype "passive"))
      (node (ref "R1_BAT") (pin "2") (pinfunction "2_2") (pintype "passive"))
    )
    (net (code "23") (name "Net-(D2-CATHODE)") (class "Default")
      (node (ref "C1_BAT1") (pin "1") (pinfunction "1_1") (pintype "passive"))
      (node (ref "D2") (pin "2") (pinfunction "CATHODE_2") (pintype "bidirectional"))
      (node (ref "IC4") (pin "1") (pinfunction "VIN_1") (pintype "bidirectional"))
      (node (ref "IC4") (pin "3") (pinfunction "CE_3") (pintype "bidirectional"))
      (node (ref "Q1") (pin "3") (pinfunction "S_3") (pintype "bidirectional"))
    )
    (net (code "24") (name "Net-(D3-A)") (class "Default")
      (node (ref "C4") (pin "1") (pinfunction "1_1") (pintype "passive"))
      (node (ref "D3") (pin "1") (pinfunction "A_1") (pintype "bidirectional"))
      (node (ref "D4") (pin "2") (pinfunction "K_2") (pintype "bidirectional"))
    )
    (net (code "25") (name "Net-(D7-CATHODE)") (class "Default")
      (node (ref "D7") (pin "2") (pinfunction "CATHODE_2") (pintype "bidirectional"))
      (node (ref "R_CAPACITOR") (pin "2") (pinfunction "2_2") (pintype "passive"))
    )
    (net (code "26") (name "Net-(EPD_C1-Pad1)") (class "Default")
      (node (ref "EPD_C1") (pin "1") (pinfunction "1_1") (pintype "passive"))
      (node (ref "J1") (pin "4") (pinfunction "4_4") (pintype "bidirectional"))
    )
    (net (code "27") (name "Net-(EPD_C2-Pad1)") (class "Default")
      (node (ref "EPD_C2") (pin "1") (pinfunction "1_1") (pintype "passive"))
      (node (ref "J1") (pin "5") (pinfunction "5_5") (pintype "bidirectional"))
    )
    (net (code "28") (name "Net-(EPD_C5-Pad1)") (class "Default")
      (node (ref "EPD_C5") (pin "1") (pinfunction "1_1") (pintype "passive"))
      (node (ref "J1") (pin "15") (pinfunction "15_15") (pintype "bidirectional"))
    )
    (net (code "29") (name "Net-(EPD_C6-Pad1)") (class "Default")
      (node (ref "EPD_C6") (pin "1") (pinfunction "1_1") (pintype "passive"))
      (node (ref "J1") (pin "18") (pinfunction "18_18") (pintype "bidirectional"))
    )
    (net (code "30") (name "Net-(EPD_C7-Pad1)") (class "Default")
      (node (ref "EPD_C7") (pin "1") (pinfunction "1_1") (pintype "passive"))
      (node (ref "J1") (pin "19") (pinfunction "19_19") (pintype "bidirectional"))
    )
    (net (code "31") (name "Net-(EPD_C8-Pad1)") (class "Default")
      (node (ref "EPD_C8") (pin "1") (pinfunction "1_1") (pintype "passive"))
      (node (ref "J1") (pin "20") (pinfunction "20_20") (pintype "bidirectional"))
    )
    (net (code "32") (name "Net-(EPD_C10-Pad1)") (class "Default")
      (node (ref "EPD_C10") (pin "1") (pinfunction "1_1") (pintype "passive"))
      (node (ref "J1") (pin "22") (pinfunction "22_22") (pintype "bidirectional"))
    )
    (net (code "33") (name "Net-(EPD_C12-Pad1)") (class "Default")
      (node (ref "EPD_C12") (pin "1") (pinfunction "1_1") (pintype "passive"))
      (node (ref "J1") (pin "24") (pinfunction "24_24") (pintype "bidirectional"))
    )
    (net (code "34") (name "Net-(IC1-CT)") (class "Default")
      (node (ref "C_DELAY") (pin "1") (pinfunction "1_1") (pintype "passive"))
      (node (ref "IC1") (pin "5") (pinfunction "CT_5") (pintype "bidirectional"))
    )
    (net (code "35") (name "Net-(J2-PadA5)") (class "Default")
      (node (ref "J2") (pin "A5") (pinfunction "A5_A5") (pintype "bidirectional"))
      (node (ref "R2-USB1") (pin "2") (pinfunction "2_2") (pintype "passive"))
    )
    (net (code "36") (name "Net-(J2-PadB5)") (class "Default")
      (node (ref "J2") (pin "B5") (pinfunction "B5_B5") (pintype "bidirectional"))
      (node (ref "R2-USB") (pin "1") (pinfunction "1_1") (pintype "passive"))
    )
    (net (code "37") (name "Net-(MCP73831-PROG)") (class "Default")
      (node (ref "MCP73831") (pin "5") (pinfunction "PROG_5") (pintype "input"))
      (node (ref "R2_BAT") (pin "2") (pinfunction "2_2") (pintype "passive"))
    )
    (net (code "38") (name "Net-(MCP73831-STAT)") (class "Default")
      (node (ref "MCP73831") (pin "1") (pinfunction "STAT_1") (pintype "output"))
      (node (ref "R1_BAT") (pin "1") (pinfunction "1_1") (pintype "passive"))
    )
    (net (code "39") (name "PREVGH") (class "Default")
      (node (ref "D5") (pin "2") (pinfunction "K_2") (pintype "bidirectional"))
      (node (ref "EPD_C9") (pin "1") (pinfunction "1_1") (pintype "passive"))
      (node (ref "J1") (pin "21") (pinfunction "21_21") (pintype "bidirectional"))
    )
    (net (code "40") (name "PREVGL") (class "Default")
      (node (ref "D4") (pin "1") (pinfunction "A_1") (pintype "bidirectional"))
      (node (ref "EPD_C11") (pin "1") (pinfunction "1_1") (pintype "passive"))
      (node (ref "J1") (pin "23") (pinfunction "23_23") (pintype "bidirectional"))
    )
    (net (code "41") (name "RESE") (class "Default")
      (node (ref "J1") (pin "3") (pinfunction "3_3") (pintype "bidirectional"))
      (node (ref "Q3") (pin "2") (pinfunction "S_2") (pintype "bidirectional"))
      (node (ref "R3") (pin "1") (pinfunction "1_1") (pintype "passive"))
    )
    (net (code "42") (name "RESE'") (class "Default")
      (node (ref "R2") (pin "2") (pinfunction "2_2") (pintype "passive"))
      (node (ref "R3") (pin "2") (pinfunction "2_2") (pintype "passive"))
      (node (ref "SJ1") (pin "2") (pinfunction "2_2") (pintype "passive"))
    )
    (net (code "43") (name "RESET") (class "Default")
      (node (ref "C5") (pin "1") (pinfunction "1_1") (pintype "passive"))
      (node (ref "IC1") (pin "1") (pinfunction "VOUT_1") (pintype "bidirectional"))
      (node (ref "RESET_BUTTON") (pin "3") (pinfunction "3_3") (pintype "passive"))
      (node (ref "RESET_BUTTON") (pin "4") (pinfunction "4_4") (pintype "passive"))
      (node (ref "R_RESET") (pin "2") (pinfunction "2_2") (pintype "passive"))
      (node (ref "U2") (pin "3") (pinfunction "EN_3") (pintype "input"))
    )
    (net (code "44") (name "RTC_RST") (class "Default")
      (node (ref "U2") (pin "16") (pinfunction "IO18_16") (pintype "bidirectional"))
      (node (ref "U3") (pin "4") (pinfunction "~{RST}_4") (pintype "input"))
    )
    (net (code "45") (name "RX") (class "Default")
      (node (ref "TP2") (pin "TP") (pinfunction "TP_TP") (pintype "input"))
      (node (ref "U2") (pin "24") (pinfunction "RXD0/GPIO17_24") (pintype "bidirectional"))
    )
    (net (code "46") (name "SCK") (class "Default")
      (node (ref "D10") (pin "1") (pinfunction "1_1") (pintype "passive"))
      (node (ref "J1") (pin "13") (pinfunction "13_13") (pintype "bidirectional"))
      (node (ref "J4") (pin "P5") (pinfunction "CLK_P5") (pintype "bidirectional"))
      (node (ref "R6") (pin "1") (pinfunction "1_1") (pintype "passive"))
      (node (ref "TP8") (pin "TP") (pinfunction "TP_TP") (pintype "input"))
      (node (ref "U1") (pin "6") (pinfunction "CLK_6") (pintype "input"))
      (node (ref "U2") (pin "6") (pinfunction "IO6_6") (pintype "bidirectional"))
    )
    (net (code "47") (name "SCL") (class "Default")
      (node (ref "J3") (pin "4") (pinfunction "4_4") (pintype "passive"))
      (node (ref "R2-PINH") (pin "1") (pinfunction "1_1") (pintype "passive"))
      (node (ref "SENSOR2") (pin "4") (pinfunction "SCK_4") (pintype "input"))
      (node (ref "U2") (pin "20") (pinfunction "IO22_20") (pintype "bidirectional"))
      (node (ref "U3") (pin "16") (pinfunction "SCL_16") (pintype "input"))
      (node (ref "U4") (pin "7") (pinfunction "SCL_7") (pintype "input"))
    )
    (net (code "48") (name "SDA") (class "Default")
      (node (ref "J3") (pin "3") (pinfunction "3_3") (pintype "passive"))
      (node (ref "R1-PINH") (pin "1") (pinfunction "1_1") (pintype "passive"))
      (node (ref "SENSOR2") (pin "3") (pinfunction "SDI_3") (pintype "bidirectional"))
      (node (ref "U2") (pin "19") (pinfunction "IO21_19") (pintype "bidirectional"))
      (node (ref "U3") (pin "15") (pinfunction "SDA_15") (pintype "bidirectional"))
      (node (ref "U4") (pin "8") (pinfunction "SDA_8") (pintype "bidirectional"))
    )
    (net (code "49") (name "SRC") (class "Default")
      (node (ref "C4") (pin "2") (pinfunction "2_2") (pintype "passive"))
      (node (ref "D5") (pin "1") (pinfunction "A_1") (pintype "bidirectional"))
      (node (ref "L1") (pin "1") (pinfunction "1_1") (pintype "passive"))
      (node (ref "Q3") (pin "3") (pinfunction "D_3") (pintype "bidirectional"))
    )
    (net (code "50") (name "SS_SD") (class "Default")
      (node (ref "D8") (pin "1") (pinfunction "1_1") (pintype "passive"))
      (node (ref "J4") (pin "P2") (pinfunction "CD/DAT3_P2") (pintype "bidirectional"))
      (node (ref "R10") (pin "1") (pinfunction "1_1") (pintype "passive"))
      (node (ref "U2") (pin "4") (pinfunction "IO4_4") (pintype "bidirectional"))
    )
    (net (code "51") (name "TX") (class "Default")
      (node (ref "TP1") (pin "TP") (pinfunction "TP_TP") (pintype "input"))
      (node (ref "U2") (pin "25") (pinfunction "TXD0/GPIO16_25") (pintype "bidirectional"))
    )
    (net (code "52") (name "USB_D+") (class "Default")
      (node (ref "D1") (pin "1") (pinfunction "I/O1_1_1") (pintype "bidirectional"))
      (node (ref "U2") (pin "14") (pinfunction "IO13_14") (pintype "bidirectional"))
    )
    (net (code "53") (name "USB_D-") (class "Default")
      (node (ref "D1") (pin "3") (pinfunction "I/O2_1_3") (pintype "bidirectional"))
      (node (ref "U2") (pin "13") (pinfunction "IO12_13") (pintype "bidirectional"))
    )
    (net (code "54") (name "VBAT") (class "Default")
      (node (ref "C2_BAT") (pin "1") (pinfunction "1_1") (pintype "passive"))
      (node (ref "MCP73831") (pin "3") (pinfunction "VBAT_3") (pintype "power_in"))
      (node (ref "Q1") (pin "1") (pinfunction "D_1") (pintype "bidirectional"))
      (node (ref "TP3") (pin "TP") (pinfunction "TP_TP") (pintype "input"))
      (node (ref "U4") (pin "2") (pinfunction "CELL_2") (pintype "power_in"))
      (node (ref "U4") (pin "3") (pinfunction "VDD_3") (pintype "power_in"))
    )
    (net (code "55") (name "VBUS") (class "Default")
      (node (ref "C1_BAT") (pin "1") (pinfunction "1_1") (pintype "passive"))
      (node (ref "C4_USB") (pin "1") (pinfunction "1_1") (pintype "passive"))
      (node (ref "C5_USB") (pin "1") (pinfunction "1_1") (pintype "passive"))
      (node (ref "CHG_LED") (pin "A") (pinfunction "A_A") (pintype "passive"))
      (node (ref "D1") (pin "5") (pinfunction "VBUS_5") (pintype "bidirectional"))
      (node (ref "D2") (pin "1") (pinfunction "ANODE_1") (pintype "bidirectional"))
      (node (ref "MCP73831") (pin "4") (pinfunction "VIN_4") (pintype "power_in"))
      (node (ref "PFMF.050.1") (pin "2") (pinfunction "2_2") (pintype "passive"))
      (node (ref "Q1") (pin "2") (pinfunction "G_2") (pintype "bidirectional"))
      (node (ref "R1_PWRUSB") (pin "2") (pinfunction "2_2") (pintype "passive"))
      (node (ref "TP14") (pin "TP") (pinfunction "TP_TP") (pintype "input"))
    )
    (net (code "56") (name "VRTC") (class "Default")
      (node (ref "C10_SUPERCAP") (pin "2") (pinfunction "2_2") (pintype "passive"))
      (node (ref "C8") (pin "1") (pinfunction "1_1") (pintype "passive"))
      (node (ref "R_CAPACITOR") (pin "1") (pinfunction "1_1") (pintype "passive"))
      (node (ref "U3") (pin "14") (pinfunction "VBAT_14") (pintype "power_in"))
    )
    (net (code "57") (name "VUSB") (class "Default")
      (node (ref "J2") (pin "A4") (pinfunction "A4_A4") (pintype "bidirectional"))
      (node (ref "J2") (pin "A9") (pinfunction "A9_A9") (pintype "bidirectional"))
      (node (ref "J2") (pin "B4") (pinfunction "B4_B4") (pintype "bidirectional"))
      (node (ref "J2") (pin "B9") (pinfunction "B9_B9") (pintype "bidirectional"))
      (node (ref "PFMF.050.1") (pin "1") (pinfunction "1_1") (pintype "passive"))
    )
    (net (code "58") (name "unconnected-(IC1-NC-Pad4)") (class "Default")
      (node (ref "IC1") (pin "4") (pinfunction "NC_4") (pintype "no_connect"))
    )
    (net (code "59") (name "unconnected-(IC4-NC-Pad4)") (class "Default")
      (node (ref "IC4") (pin "4") (pinfunction "NC_4") (pintype "no_connect"))
    )
    (net (code "60") (name "unconnected-(J1-Pad1)") (class "Default")
      (node (ref "J1") (pin "1") (pinfunction "1_1") (pintype "bidirectional"))
    )
    (net (code "61") (name "unconnected-(J1-Pad6)") (class "Default")
      (node (ref "J1") (pin "6") (pinfunction "6_6") (pintype "bidirectional"))
    )
    (net (code "62") (name "unconnected-(J1-Pad7)") (class "Default")
      (node (ref "J1") (pin "7") (pinfunction "7_7") (pintype "bidirectional"))
    )
    (net (code "63") (name "unconnected-(J2-PadA8)") (class "Default")
      (node (ref "J2") (pin "A8") (pinfunction "A8_A8") (pintype "bidirectional"))
    )
    (net (code "64") (name "unconnected-(J2-PadB8)") (class "Default")
      (node (ref "J2") (pin "B8") (pinfunction "B8_B8") (pintype "bidirectional"))
    )
    (net (code "65") (name "unconnected-(J4-DAT1-PadP8)") (class "Default")
      (node (ref "J4") (pin "P8") (pinfunction "DAT1_P8") (pintype "bidirectional"))
    )
    (net (code "66") (name "unconnected-(J4-DAT2-PadP1)") (class "Default")
      (node (ref "J4") (pin "P1") (pinfunction "DAT2_P1") (pintype "bidirectional"))
    )
    (net (code "67") (name "unconnected-(J4-DETECTION_1-PadS1)") (class "Default")
      (node (ref "J4") (pin "S1") (pinfunction "DETECTION_1_S1") (pintype "bidirectional"))
    )
    (net (code "68") (name "unconnected-(J4-DETECTION_2-PadS2)") (class "Default")
      (node (ref "J4") (pin "S2") (pinfunction "DETECTION_2_S2") (pintype "bidirectional"))
    )
    (net (code "69") (name "unconnected-(U2-NC-Pad22)") (class "Default")
      (node (ref "U2") (pin "22") (pinfunction "NC_22") (pintype "no_connect"))
    )
    (net (code "70") (name "unconnected-(U4-~{ALERT}-Pad5)") (class "Default")
      (node (ref "U4") (pin "5") (pinfunction "~{ALERT}_5") (pintype "output"))
    )
  )
)
